# ControlUnit.net
KiCad netlist of a schematic drawn in Altium Designer
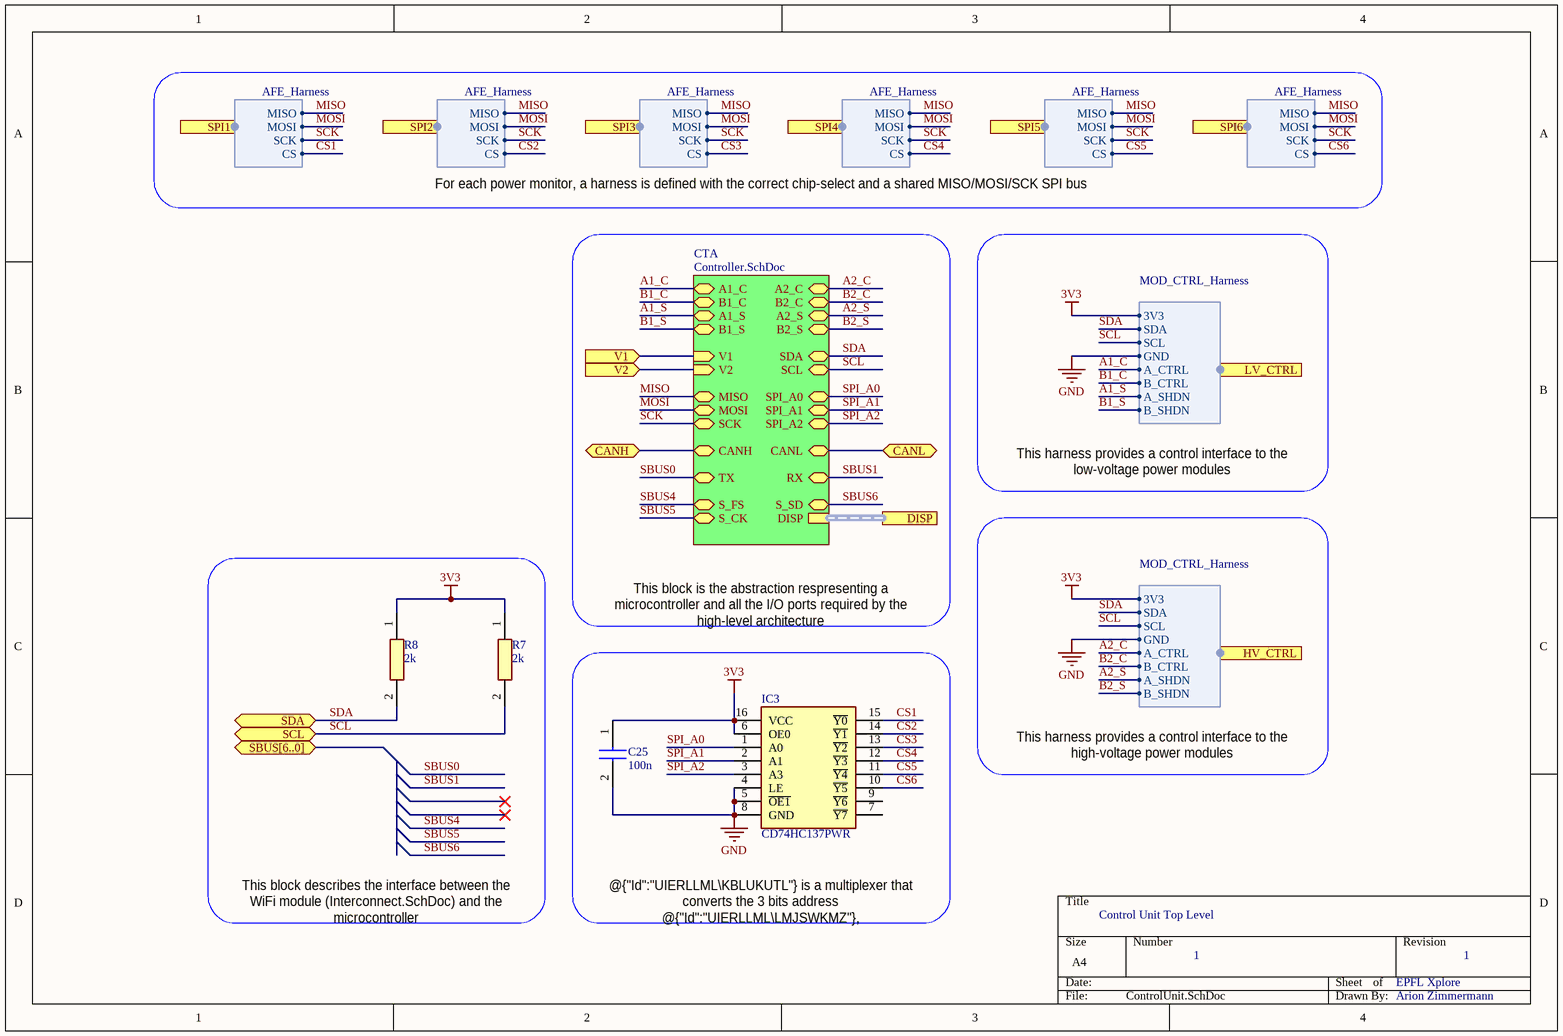
[diagram p0: ControlUnit.SchDoc]

(export (version "E")
  (design (tool "Eeschema 10.0.6"))
  (components
    (comp (ref "C25")
      (value "100n")
      (footprint "SamacSys:CAPC1608X95N")
      (description "Capacitor")
      (fields
        (field (name "MANUFACTURER_PART_NUMBER") "C0603C104K5RACTU")
        (field (name "MOUSER PART NUMBER") "80-C0603C104K5R")
      )
      (libsource (lib "CarrierBoard") (part "C0603C104K5RACTU"))
    )
    (comp (ref "IC3")
      (value "CD74HC137PWR")
      (footprint "SamacSys:SOP65P640X120-16N")
      (description "Integrated Circuit")
      (fields (field (name "MOUSER PART NUMBER") "595-CD74HC137PWR"))
      (libsource (lib "*") (part "CD74HC137PWR"))
    )
    (comp (ref "R7")
      (value "2k")
      (footprint "SamacSys:RESC1608X50N")
      (description "Resistor")
      (fields
        (field (name "MANUFACTURER_PART_NUMBER") "CRCW0603787RFKEA")
        (field (name "Comment") "CRCW06032K00JNEB")
      )
      (libsource (lib "CarrierBoard") (part "CRCW0603931RFKEA"))
    )
    (comp (ref "R8")
      (value "2k")
      (footprint "SamacSys:RESC1608X50N")
      (description "Resistor")
      (fields
        (field (name "MANUFACTURER_PART_NUMBER") "CRCW0603787RFKEA")
        (field (name "Comment") "CRCW06032K00JNEB")
      )
      (libsource (lib "CarrierBoard") (part "CRCW0603931RFKEA"))
    )
  )
  (nets
    (net (code "16") (name "/CS1") (class "Default")
      (node (ref "IC3") (pin "15") (pinfunction "~{Y0}_15") (pintype "passive"))
    )
    (net (code "17") (name "/CS2") (class "Default")
      (node (ref "IC3") (pin "14") (pinfunction "~{Y1}_14") (pintype "passive"))
    )
    (net (code "18") (name "/CS3") (class "Default")
      (node (ref "IC3") (pin "13") (pinfunction "~{Y2}_13") (pintype "passive"))
    )
    (net (code "19") (name "/CS4") (class "Default")
      (node (ref "IC3") (pin "12") (pinfunction "~{Y3}_12") (pintype "passive"))
    )
    (net (code "20") (name "/CS5") (class "Default")
      (node (ref "IC3") (pin "11") (pinfunction "~{Y4}_11") (pintype "passive"))
    )
    (net (code "21") (name "/CS6") (class "Default")
      (node (ref "IC3") (pin "10") (pinfunction "~{Y5}_10") (pintype "passive"))
    )
    (net (code "32") (name "/SCL") (class "Default")
      (node (ref "R7") (pin "2") (pinfunction "2_2") (pintype "passive"))
    )
    (net (code "33") (name "/SDA") (class "Default")
      (node (ref "R8") (pin "2") (pinfunction "2_2") (pintype "passive"))
    )
    (net (code "34") (name "/SPI_A0") (class "Default")
      (node (ref "IC3") (pin "1") (pinfunction "A0_1") (pintype "passive"))
    )
    (net (code "35") (name "/SPI_A1") (class "Default")
      (node (ref "IC3") (pin "2") (pinfunction "A1_2") (pintype "passive"))
    )
    (net (code "36") (name "/SPI_A2") (class "Default")
      (node (ref "IC3") (pin "3") (pinfunction "A3_3") (pintype "passive"))
    )
    (net (code "41") (name "3V3") (class "Default")
      (node (ref "C25") (pin "1") (pinfunction "1_1") (pintype "passive"))
      (node (ref "IC3") (pin "16") (pinfunction "VCC_16") (pintype "passive"))
      (node (ref "IC3") (pin "6") (pinfunction "OE0_6") (pintype "passive"))
      (node (ref "R7") (pin "1") (pinfunction "1_1") (pintype "passive"))
      (node (ref "R8") (pin "1") (pinfunction "1_1") (pintype "passive"))
    )
    (net (code "42") (name "GND") (class "Default")
      (node (ref "C25") (pin "2") (pinfunction "2_2") (pintype "passive"))
      (node (ref "IC3") (pin "4") (pinfunction "LE_4") (pintype "passive"))
      (node (ref "IC3") (pin "5") (pinfunction "~{OE1}_5") (pintype "passive"))
      (node (ref "IC3") (pin "8") (pinfunction "GND_8") (pintype "passive"))
    )
    (net (code "43") (name "unconnected-(IC3-~{Y6}-Pad9)") (class "Default")
      (node (ref "IC3") (pin "9") (pinfunction "~{Y6}_9") (pintype "passive"))
    )
    (net (code "44") (name "unconnected-(IC3-~{Y7}-Pad7)") (class "Default")
      (node (ref "IC3") (pin "7") (pinfunction "~{Y7}_7") (pintype "passive"))
    )
  )
)
